# ESP03_Breakout.net
KiCad netlist of a schematic drawn in EAGLE
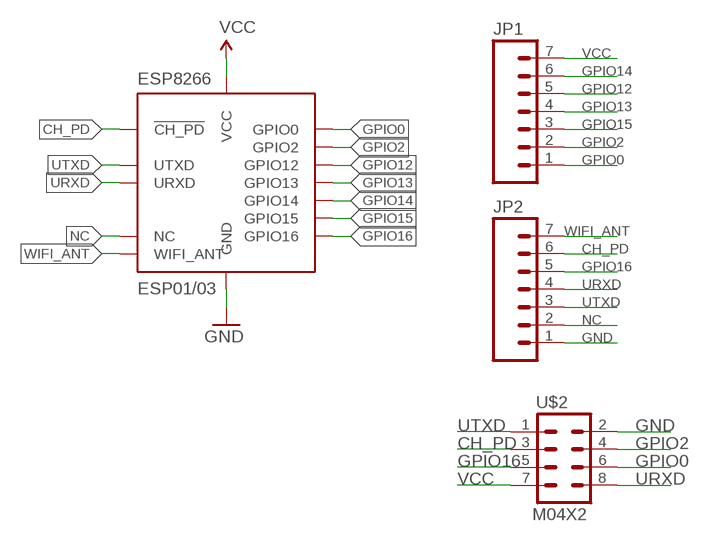
[diagram p0: schematic, sheet 1]

(export (version "E")
  (design (tool "Eeschema 10.0.6"))
  (components
    (comp (ref "ESP8266")
      (value "ESP01/03")
      (footprint "eagle-import:ESP-03")
      (libsource (lib "eagle-import") (part "ESP-03SMD"))
    )
    (comp (ref "JP1")
      (value "M07")
      (footprint "eagle-import:1X07")
      (libsource (lib "eagle-import") (part "M07"))
    )
    (comp (ref "JP2")
      (value "M07")
      (footprint "eagle-import:1X07")
      (libsource (lib "eagle-import") (part "M07"))
    )
    (comp (ref "U$2")
      (value "M04X2")
      (footprint "eagle-import:2X4")
      (libsource (lib "eagle-import") (part "M04X2"))
    )
  )
  (nets
    (net (code "1") (name "CH_PD") (class "Default")
      (node (ref "ESP8266") (pin "CH_PD") (pinfunction "~{CH_PD}_CH_PD") (pintype "input"))
      (node (ref "JP2") (pin "6") (pinfunction "6_6") (pintype "passive"))
      (node (ref "U$2") (pin "3") (pinfunction "3_3") (pintype "passive"))
    )
    (net (code "2") (name "GND") (class "Default")
      (node (ref "ESP8266") (pin "GND") (pinfunction "GND_GND") (pintype "power_in"))
      (node (ref "JP2") (pin "1") (pinfunction "1_1") (pintype "passive"))
      (node (ref "U$2") (pin "2") (pinfunction "2_2") (pintype "passive"))
    )
    (net (code "3") (name "GPIO0") (class "Default")
      (node (ref "ESP8266") (pin "GPIO0") (pinfunction "GPIO0_GPIO0") (pintype "bidirectional"))
      (node (ref "JP1") (pin "1") (pinfunction "1_1") (pintype "passive"))
      (node (ref "U$2") (pin "6") (pinfunction "6_6") (pintype "passive"))
    )
    (net (code "4") (name "GPIO2") (class "Default")
      (node (ref "ESP8266") (pin "GPIO2") (pinfunction "GPIO2_GPIO2") (pintype "bidirectional"))
      (node (ref "JP1") (pin "2") (pinfunction "2_2") (pintype "passive"))
      (node (ref "U$2") (pin "4") (pinfunction "4_4") (pintype "passive"))
    )
    (net (code "5") (name "GPIO12") (class "Default")
      (node (ref "ESP8266") (pin "GPIO12") (pinfunction "GPIO12_GPIO12") (pintype "bidirectional"))
      (node (ref "JP1") (pin "5") (pinfunction "5_5") (pintype "passive"))
    )
    (net (code "6") (name "GPIO13") (class "Default")
      (node (ref "ESP8266") (pin "GPIO13") (pinfunction "GPIO13_GPIO13") (pintype "bidirectional"))
      (node (ref "JP1") (pin "4") (pinfunction "4_4") (pintype "passive"))
    )
    (net (code "7") (name "GPIO14") (class "Default")
      (node (ref "ESP8266") (pin "GPIO14") (pinfunction "GPIO14_GPIO14") (pintype "bidirectional"))
      (node (ref "JP1") (pin "6") (pinfunction "6_6") (pintype "passive"))
    )
    (net (code "8") (name "GPIO15") (class "Default")
      (node (ref "ESP8266") (pin "GPIO15") (pinfunction "GPIO15_GPIO15") (pintype "bidirectional"))
      (node (ref "JP1") (pin "3") (pinfunction "3_3") (pintype "passive"))
    )
    (net (code "9") (name "GPIO16") (class "Default")
      (node (ref "ESP8266") (pin "GPIO16") (pinfunction "GPIO16_GPIO16") (pintype "bidirectional"))
      (node (ref "JP2") (pin "5") (pinfunction "5_5") (pintype "passive"))
      (node (ref "U$2") (pin "5") (pinfunction "5_5") (pintype "passive"))
    )
    (net (code "10") (name "NC") (class "Default")
      (node (ref "ESP8266") (pin "NC") (pinfunction "NC_NC") (pintype "input"))
      (node (ref "JP2") (pin "2") (pinfunction "2_2") (pintype "passive"))
    )
    (net (code "11") (name "URXD") (class "Default")
      (node (ref "ESP8266") (pin "URXD") (pinfunction "URXD_URXD") (pintype "input"))
      (node (ref "JP2") (pin "4") (pinfunction "4_4") (pintype "passive"))
      (node (ref "U$2") (pin "8") (pinfunction "8_8") (pintype "passive"))
    )
    (net (code "12") (name "UTXD") (class "Default")
      (node (ref "ESP8266") (pin "UTXD") (pinfunction "UTXD_UTXD") (pintype "output"))
      (node (ref "JP2") (pin "3") (pinfunction "3_3") (pintype "passive"))
      (node (ref "U$2") (pin "1") (pinfunction "1_1") (pintype "passive"))
    )
    (net (code "13") (name "VCC") (class "Default")
      (node (ref "ESP8266") (pin "VCC") (pinfunction "VCC_VCC") (pintype "power_in"))
      (node (ref "JP1") (pin "7") (pinfunction "7_7") (pintype "passive"))
      (node (ref "U$2") (pin "7") (pinfunction "7_7") (pintype "passive"))
    )
    (net (code "14") (name "WIFI_ANT") (class "Default")
      (node (ref "ESP8266") (pin "WIFI_ANT") (pinfunction "WIFI_ANT_WIFI_ANT") (pintype "bidirectional"))
      (node (ref "JP2") (pin "7") (pinfunction "7_7") (pintype "passive"))
    )
  )
)
